# 02_EFR32xG1x_DISC_REF_DES_A00_RfAntPower.net
KiCad netlist of a schematic drawn in Altium Designer
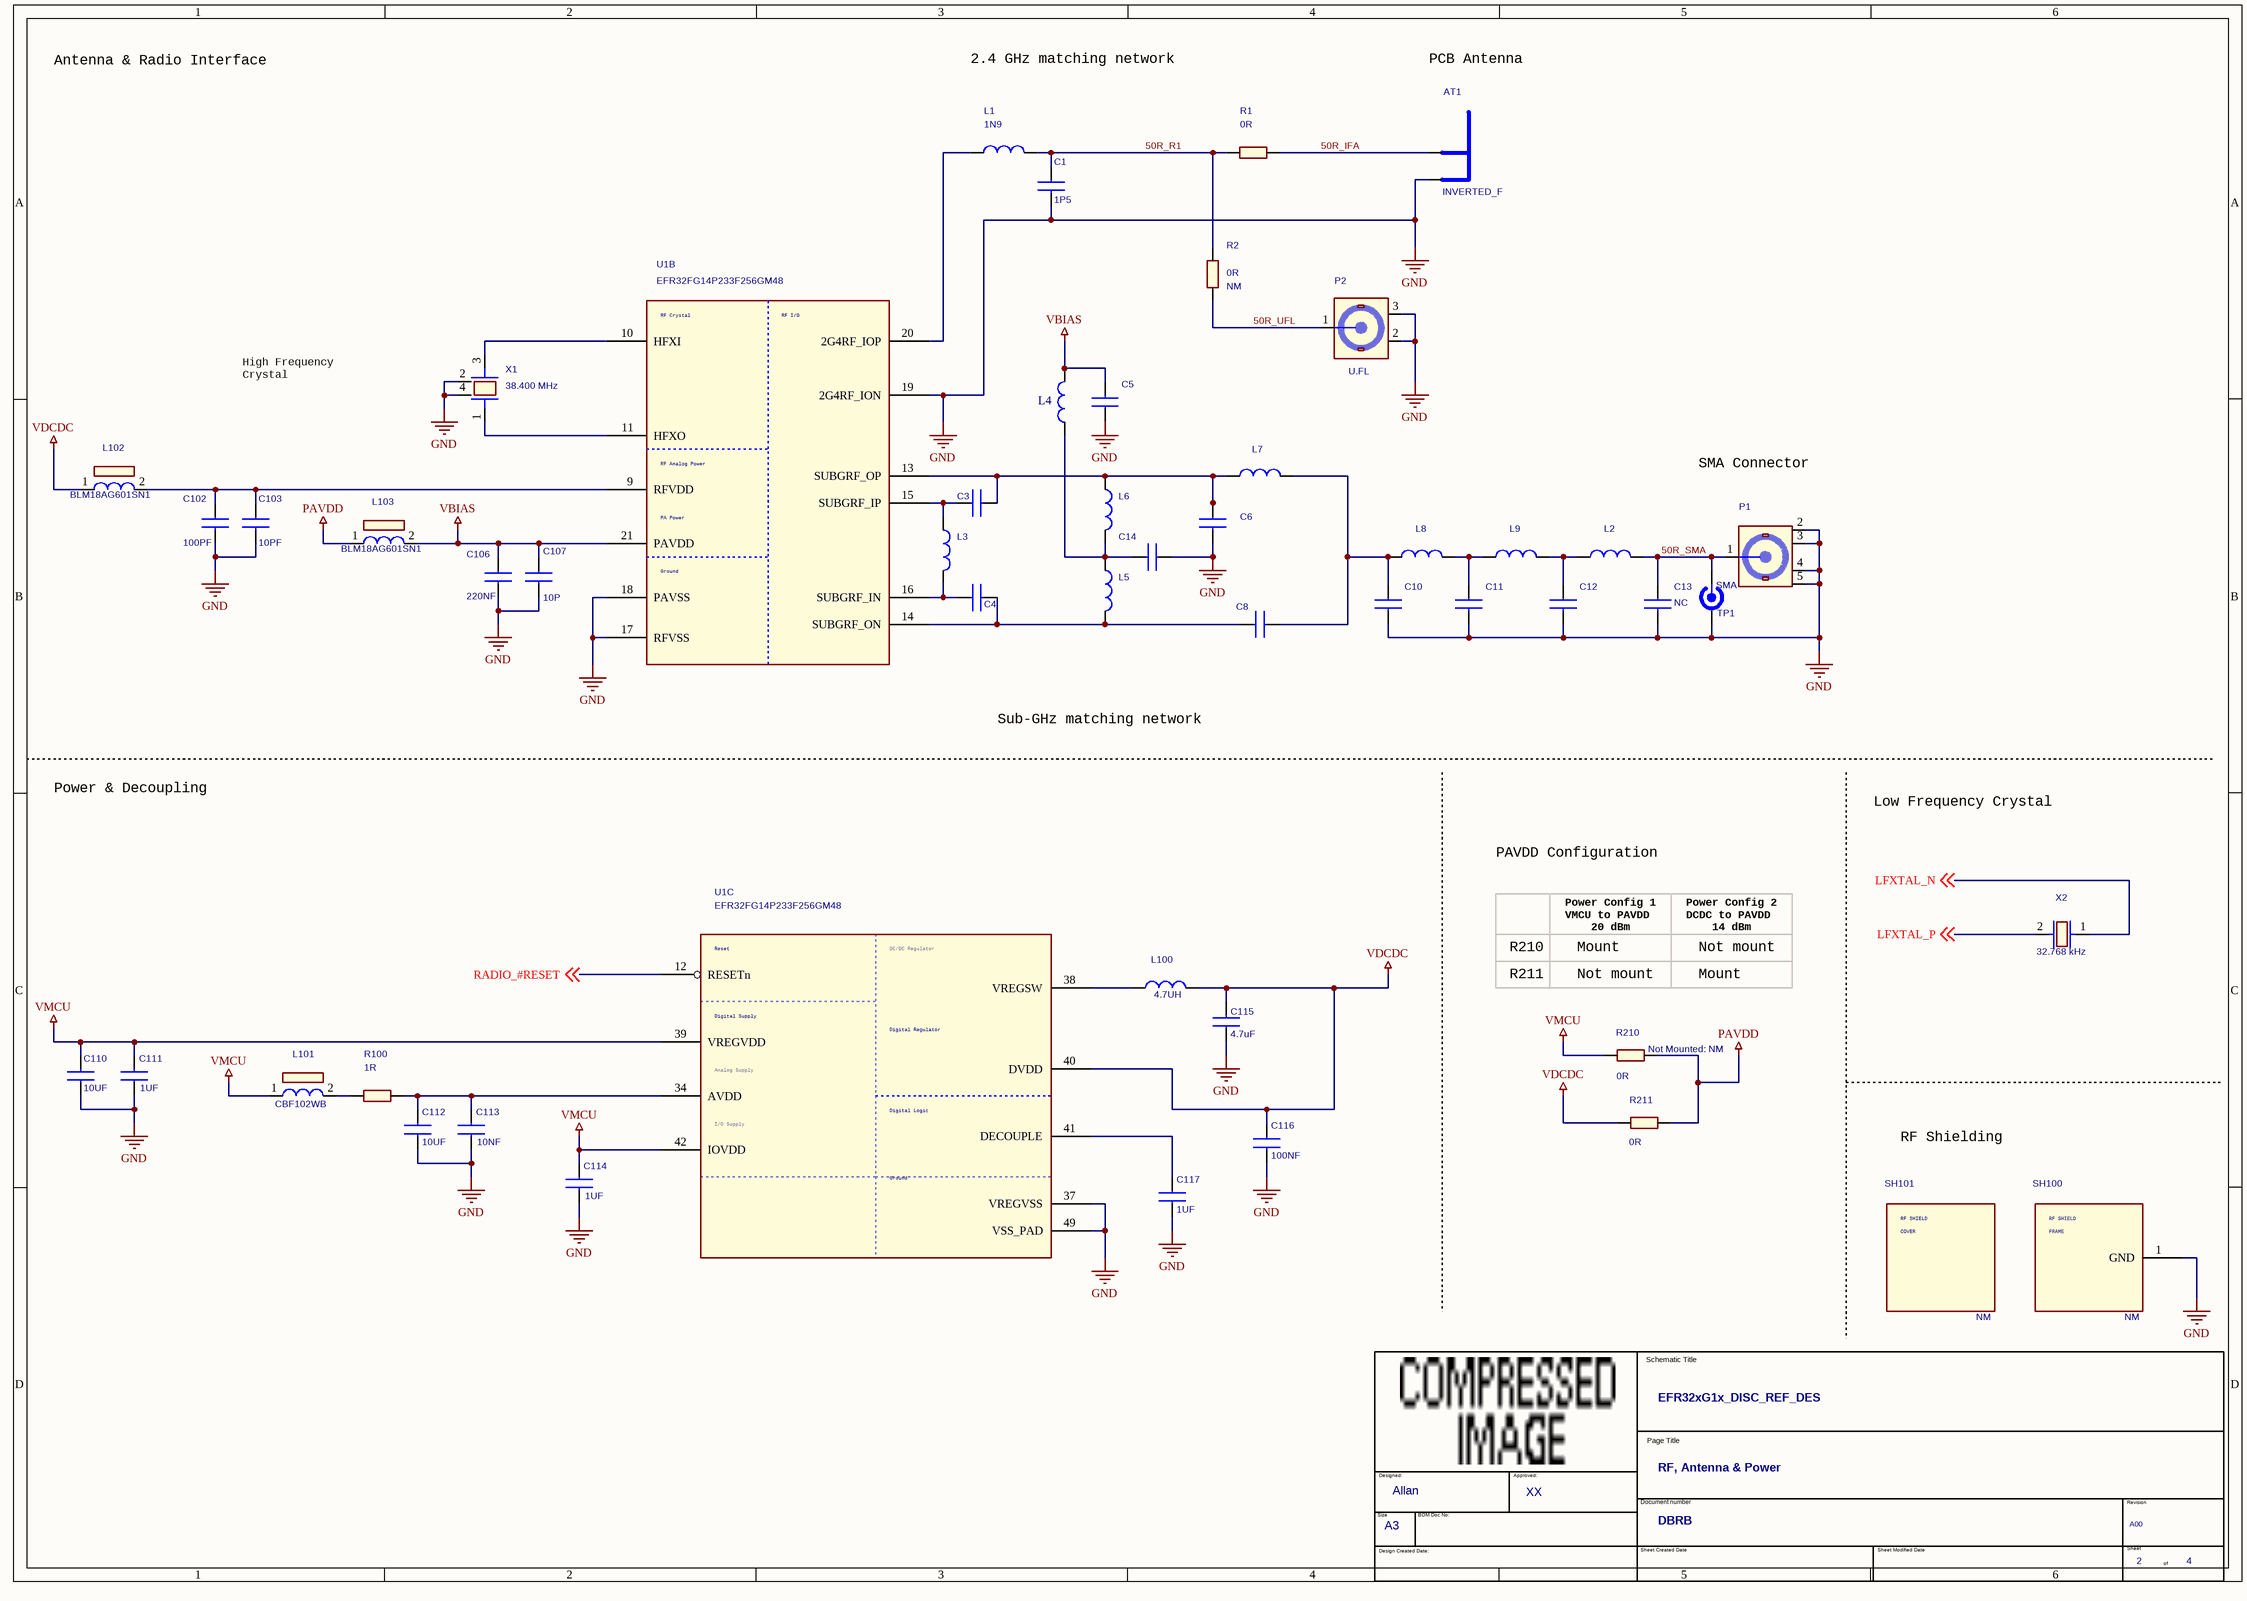
[diagram p0: 02_EFR32xG1x_DISC_REF_DES_A00_RfAntPower.SchDoc]

(export (version "E")
  (design (tool "Eeschema 10.0.6"))
  (components
    (comp (ref "AT1")
      (value "INVERTED_F")
      (footprint "ANT_INV_F_2.4_GHZ_17.3MM_MIR")
      (libsource (lib "*") (part "ANT_INVERTED_F"))
    )
    (comp (ref "C1")
      (value "1P5")
      (footprint "C0201_L")
      (fields (field (name "TOLERANCE") "?.05P") (field (name "MFG") "Murata"))
      (libsource (lib "*") (part "C0402"))
    )
    (comp (ref "C3")
      (value "1P8")
      (footprint "C0201_L")
      (fields (field (name "TOLERANCE") "?.05P") (field (name "MFG") "Murata"))
      (libsource (lib "*") (part "C0402"))
    )
    (comp (ref "C4")
      (value "1P8")
      (footprint "C0201_L")
      (fields (field (name "TOLERANCE") "?.05P") (field (name "MFG") "Murata"))
      (libsource (lib "*") (part "C0402"))
    )
    (comp (ref "C5")
      (value "270pF")
      (footprint "C0201_L")
      (fields (field (name "TOLERANCE") "?.1P") (field (name "MFG") "Murata"))
      (libsource (lib "*") (part "C0402"))
    )
    (comp (ref "C6") (value "5.1P") (footprint "C0201_L") (libsource (lib "*") (part "C0402")))
    (comp (ref "C8")
      (value "4P7")
      (footprint "C0201_L")
      (fields (field (name "TOLERANCE") "?%") (field (name "MFG") "Murata"))
      (libsource (lib "*") (part "C0402"))
    )
    (comp (ref "C10")
      (value "6P2")
      (footprint "C0201_L")
      (fields (field (name "TOLERANCE") "?.1P") (field (name "MFG") "Murata"))
      (libsource (lib "*") (part "C0402"))
    )
    (comp (ref "C11")
      (value "5.6P")
      (footprint "C0201_L")
      (fields (field (name "TOLERANCE") "?%") (field (name "MFG") "Murata"))
      (libsource (lib "*") (part "C0402"))
    )
    (comp (ref "C12")
      (value "5P6")
      (footprint "C0201_L")
      (fields (field (name "TOLERANCE") "?.05pF") (field (name "MFG") "Murata"))
      (libsource (lib "*") (part "C0402"))
    )
    (comp (ref "C13")
      (value "NC")
      (footprint "C0201_L")
      (fields (field (name "TOLERANCE") "?.05pF") (field (name "MFG") "Murata"))
      (libsource (lib "*") (part "C0402"))
    )
    (comp (ref "C14")
      (value "2P")
      (footprint "C0201_L")
      (fields (field (name "TOLERANCE") "?%") (field (name "MFG") "Murata"))
      (libsource (lib "*") (part "C0402"))
    )
    (comp (ref "C102")
      (value "100PF")
      (footprint "C0402_L")
      (fields (field (name "TOLERANCE") "5%"))
      (libsource (lib "*") (part "C0402"))
    )
    (comp (ref "C103")
      (value "10PF")
      (footprint "C0402_L")
      (fields (field (name "TOLERANCE") "5%"))
      (libsource (lib "*") (part "C0402"))
    )
    (comp (ref "C106")
      (value "220NF")
      (footprint "C0402_L")
      (fields (field (name "TOLERANCE") "10%"))
      (libsource (lib "*") (part "C0402"))
    )
    (comp (ref "C107")
      (value "10P")
      (footprint "C0201_L")
      (fields (field (name "TOLERANCE") "5%"))
      (libsource (lib "*") (part "C0402"))
    )
    (comp (ref "C110")
      (value "10UF")
      (footprint "C0603_L")
      (fields (field (name "TOLERANCE") "20%"))
      (libsource (lib "*") (part "C0603"))
    )
    (comp (ref "C111")
      (value "1UF")
      (footprint "C0402_L")
      (fields (field (name "TOLERANCE") "10%"))
      (libsource (lib "*") (part "C0402"))
    )
    (comp (ref "C112")
      (value "10UF")
      (footprint "C0603_L")
      (fields (field (name "TOLERANCE") "20%"))
      (libsource (lib "*") (part "C0603"))
    )
    (comp (ref "C113")
      (value "10NF")
      (footprint "C0402_L")
      (fields (field (name "TOLERANCE") "10%"))
      (libsource (lib "*") (part "C0402"))
    )
    (comp (ref "C114")
      (value "1UF")
      (footprint "C0402_L")
      (fields (field (name "TOLERANCE") "10%"))
      (libsource (lib "*") (part "C0402"))
    )
    (comp (ref "C115")
      (value "4.7uF")
      (footprint "C0402_L")
      (fields (field (name "TOLERANCE") "10%"))
      (libsource (lib "*") (part "C0402"))
    )
    (comp (ref "C116")
      (value "100NF")
      (footprint "C0402_L")
      (fields (field (name "TOLERANCE") "10%"))
      (libsource (lib "*") (part "C0402"))
    )
    (comp (ref "C117")
      (value "1UF")
      (footprint "C0402_L")
      (fields (field (name "TOLERANCE") "10%"))
      (libsource (lib "*") (part "C0402"))
    )
    (comp (ref "L1")
      (value "1N9")
      (footprint "COIL_0201_L")
      (fields (field (name "MFG") "Murata") (field (name "TOLERANCE") "?.05N"))
      (libsource (lib "") (part "L0402_1"))
    )
    (comp (ref "L2")
      (value "120P")
      (footprint "COIL_0201_L")
      (fields (field (name "MFG") "Murata") (field (name "TOLERANCE") "?%"))
      (libsource (lib "*") (part "L0402"))
    )
    (comp (ref "L3") (value "75NH") (footprint "COIL_0201_L") (libsource (lib "BRD4259B") (part "L0402")))
    (comp (ref "L4")
      (value "330NH")
      (footprint "COIL_0402_L")
      (libsource (lib "BRD4259A_Library") (part "L0603"))
    )
    (comp (ref "L5")
      (value "12NH")
      (footprint "COIL_0201_L")
      (libsource (lib "BRD4259A_Library") (part "L0402"))
    )
    (comp (ref "L6")
      (value "12NH")
      (footprint "COIL_0201_L")
      (libsource (lib "BRD4259A_Library") (part "L0402"))
    )
    (comp (ref "L7")
      (value "27NH")
      (footprint "COIL_0201_L")
      (fields (field (name "MFG") "Murata") (field (name "TOLERANCE") "?%"))
      (libsource (lib "*") (part "L0402"))
    )
    (comp (ref "L8")
      (value "24NH")
      (footprint "COIL_0201_L")
      (fields (field (name "MFG") "Murata") (field (name "TOLERANCE") "?%"))
      (libsource (lib "*") (part "L0402"))
    )
    (comp (ref "L9")
      (value "24NH")
      (footprint "COIL_0201_L")
      (fields (field (name "MFG") "Murata") (field (name "TOLERANCE") "?%"))
      (libsource (lib "*") (part "L0402"))
    )
    (comp (ref "L100")
      (value "4.7UH")
      (footprint "COIL_MUR_LQH3NP_1212")
      (fields (field (name "MFG") "Murata"))
      (libsource (lib "*") (part "LQH3NP"))
    )
    (comp (ref "L101")
      (value "CBF102WB")
      (footprint "WURTH_CBF_0603")
      (fields (field (name "MFG") "W黵th Electronics"))
      (libsource (lib "*") (part "CBF102WB"))
    )
    (comp (ref "L102")
      (value "BLM18AG601SN1")
      (footprint "COIL_MUR_BLM18_0603")
      (fields (field (name "MFG") "Murata"))
      (libsource (lib "*") (part "BLM18AG"))
    )
    (comp (ref "L103")
      (value "BLM18AG601SN1")
      (footprint "COIL_MUR_BLM18_0603")
      (fields (field (name "MFG") "Murata"))
      (libsource (lib "*") (part "BLM18AG"))
    )
    (comp (ref "P1")
      (value "SMA")
      (footprint "TE_SMA_TH_1814832")
      (fields (field (name "MFG") "TE Connectivity"))
      (libsource (lib "*") (part "SMA_TH"))
    )
    (comp (ref "P2")
      (value "U.FL")
      (footprint "HIROSE_U.FL-R-SMT-1")
      (fields (field (name "MFG") "Hirose"))
      (libsource (lib "*") (part "HIROSE_U.FL"))
    )
    (comp (ref "R1") (value "0R") (footprint "R0402_L") (libsource (lib "") (part "R0402_2")))
    (comp (ref "R2")
      (value "0R")
      (footprint "R0402_L")
      (fields (field (name "NOT MOUNTED") "NM"))
      (libsource (lib "*") (part "R0402"))
    )
    (comp (ref "R100") (value "1R") (footprint "R0402_L") (libsource (lib "") (part "R0402_2")))
    (comp (ref "R210")
      (value "0R")
      (footprint "R0402_L")
      (fields (field (name "NOT MOUNTED") "NM"))
      (libsource (lib "") (part "R0402_1"))
    )
    (comp (ref "R211") (value "0R") (footprint "R0402_L") (libsource (lib "") (part "R0402_1")))
    (comp (ref "SH100")
      (value "RF_SHIELD_FRAME_BMI-S-203-F")
      (footprint "RF_SHIELD_FRAME_BMI-S-203-F_PCB4100")
      (fields (field (name "MFG") "Laird Technologies") (field (name "NOT MOUNTED") "NM"))
      (libsource (lib "*") (part "RF_SHIELD_FRAME_BMI-S-203-F"))
    )
    (comp (ref "SH101")
      (value "RF_SHIELD_COVER_BMI-S-203-C")
      (fields (field (name "NOT MOUNTED") "NM") (field (name "MFG") "Laird Technologies"))
      (libsource (lib "*") (part "RF_SHIELD_COVER_BMI-S-203-C"))
    )
    (comp (ref "TP1")
      (value "RF_TEST_POINT")
      (footprint "TP_INGUN_50_OHM_CLOSED openvia")
      (libsource (lib "*") (part "TP_RF"))
    )
    (comp (ref "U1")
      (value "EFR32FG14P233F256GM48")
      (footprint "QFN48_M050_SQ7.0_EP_SL_L")
      (fields (field (name "MFG") "Silicon Labs"))
      (libsource (lib "*") (part "EFR32-DUALBAND-QFN48"))
    )
    (comp (ref "X1")
      (value "38.400 MHz")
      (footprint "X_SSS_DSX211SH_2.05X1.65-4")
      (fields (field (name "MFG") "KDS"))
      (libsource (lib "*") (part "DSX211SH"))
    )
    (comp (ref "X2")
      (value "32.768 kHz")
      (footprint "X_MCS_CM8V-T1A")
      (fields (field (name "MFG") "KDS"))
      (libsource (lib "*") (part "CM8V-T1A"))
    )
  )
  (nets
    (net (code "1") (name "/50R_IFA") (class "Default")
      (node (ref "AT1") (pin "1") (pinfunction "ANT_1") (pintype "passive"))
      (node (ref "R1") (pin "2") (pinfunction "2_2") (pintype "passive"))
    )
    (net (code "2") (name "/50R_R1") (class "Default")
      (node (ref "C1") (pin "2") (pinfunction "2_2") (pintype "passive"))
      (node (ref "L1") (pin "2") (pinfunction "2_2") (pintype "passive"))
      (node (ref "R1") (pin "1") (pinfunction "1_1") (pintype "passive"))
      (node (ref "R2") (pin "1") (pinfunction "1_1") (pintype "passive"))
    )
    (net (code "3") (name "/50R_SMA") (class "Default")
      (node (ref "C13") (pin "1") (pinfunction "1_1") (pintype "passive"))
      (node (ref "L2") (pin "1") (pinfunction "1_1") (pintype "passive"))
      (node (ref "P1") (pin "1") (pinfunction "SIGNAL_1") (pintype "passive"))
      (node (ref "TP1") (pin "1") (pinfunction "RF_1") (pintype "passive"))
    )
    (net (code "4") (name "/50R_UFL") (class "Default")
      (node (ref "P2") (pin "1") (pinfunction "SIGNAL_1") (pintype "passive"))
      (node (ref "R2") (pin "2") (pinfunction "2_2") (pintype "passive"))
    )
    (net (code "5") (name "GND") (class "Default")
      (node (ref "AT1") (pin "2") (pinfunction "GND_2") (pintype "passive"))
      (node (ref "C1") (pin "1") (pinfunction "1_1") (pintype "passive"))
      (node (ref "C10") (pin "2") (pinfunction "2_2") (pintype "passive"))
      (node (ref "C102") (pin "2") (pinfunction "2_2") (pintype "passive"))
      (node (ref "C103") (pin "2") (pinfunction "2_2") (pintype "passive"))
      (node (ref "C106") (pin "2") (pinfunction "2_2") (pintype "passive"))
      (node (ref "C107") (pin "2") (pinfunction "2_2") (pintype "passive"))
      (node (ref "C11") (pin "2") (pinfunction "2_2") (pintype "passive"))
      (node (ref "C110") (pin "2") (pinfunction "2_2") (pintype "passive"))
      (node (ref "C111") (pin "2") (pinfunction "2_2") (pintype "passive"))
      (node (ref "C112") (pin "2") (pinfunction "2_2") (pintype "passive"))
      (node (ref "C113") (pin "2") (pinfunction "2_2") (pintype "passive"))
      (node (ref "C114") (pin "2") (pinfunction "2_2") (pintype "passive"))
      (node (ref "C115") (pin "2") (pinfunction "2_2") (pintype "passive"))
      (node (ref "C116") (pin "2") (pinfunction "2_2") (pintype "passive"))
      (node (ref "C117") (pin "2") (pinfunction "2_2") (pintype "passive"))
      (node (ref "C12") (pin "2") (pinfunction "2_2") (pintype "passive"))
      (node (ref "C13") (pin "2") (pinfunction "2_2") (pintype "passive"))
      (node (ref "C14") (pin "2") (pinfunction "2_2") (pintype "passive"))
      (node (ref "C5") (pin "2") (pinfunction "2_2") (pintype "passive"))
      (node (ref "C6") (pin "2") (pinfunction "2_2") (pintype "passive"))
      (node (ref "P1") (pin "2") (pinfunction "GND1_2") (pintype "passive"))
      (node (ref "P1") (pin "3") (pinfunction "GND2_3") (pintype "passive"))
      (node (ref "P1") (pin "4") (pinfunction "GND3_4") (pintype "passive"))
      (node (ref "P1") (pin "5") (pinfunction "GND4_5") (pintype "passive"))
      (node (ref "P2") (pin "2") (pinfunction "GND1_2") (pintype "passive"))
      (node (ref "P2") (pin "3") (pinfunction "GND4_3") (pintype "passive"))
      (node (ref "SH100") (pin "1") (pinfunction "GND_1") (pintype "passive"))
      (node (ref "TP1") (pin "2") (pinfunction "GND_2") (pintype "power_in"))
      (node (ref "U1") (pin "17") (pinfunction "RFVSS_17") (pintype "passive"))
      (node (ref "U1") (pin "18") (pinfunction "PAVSS_18") (pintype "passive"))
      (node (ref "U1") (pin "19") (pinfunction "2G4RF_ION_19") (pintype "passive"))
      (node (ref "U1") (pin "37") (pinfunction "VREGVSS_37") (pintype "passive"))
      (node (ref "U1") (pin "49") (pinfunction "VSS_PAD_49") (pintype "power_in"))
      (node (ref "X1") (pin "2") (pinfunction "2_2") (pintype "passive"))
      (node (ref "X1") (pin "4") (pinfunction "4_4") (pintype "passive"))
    )
    (net (code "6") (name "LFXTAL_N") (class "Default")
      (node (ref "X2") (pin "1") (pinfunction "1_1") (pintype "passive"))
    )
    (net (code "7") (name "LFXTAL_P") (class "Default")
      (node (ref "X2") (pin "2") (pinfunction "2_2") (pintype "passive"))
    )
    (net (code "8") (name "Net-(C10-Pad1)") (class "Default")
      (node (ref "C10") (pin "1") (pinfunction "1_1") (pintype "passive"))
      (node (ref "C8") (pin "1") (pinfunction "1_1") (pintype "passive"))
      (node (ref "L7") (pin "1") (pinfunction "1_1") (pintype "passive"))
      (node (ref "L8") (pin "2") (pinfunction "2_2") (pintype "passive"))
    )
    (net (code "9") (name "Net-(C11-Pad1)") (class "Default")
      (node (ref "C11") (pin "1") (pinfunction "1_1") (pintype "passive"))
      (node (ref "L8") (pin "1") (pinfunction "1_1") (pintype "passive"))
      (node (ref "L9") (pin "2") (pinfunction "2_2") (pintype "passive"))
    )
    (net (code "10") (name "Net-(C12-Pad1)") (class "Default")
      (node (ref "C12") (pin "1") (pinfunction "1_1") (pintype "passive"))
      (node (ref "L2") (pin "2") (pinfunction "2_2") (pintype "passive"))
      (node (ref "L9") (pin "1") (pinfunction "1_1") (pintype "passive"))
    )
    (net (code "11") (name "Net-(C14-Pad1)") (class "Default")
      (node (ref "C14") (pin "1") (pinfunction "1_1") (pintype "passive"))
      (node (ref "L4") (pin "2") (pinfunction "2_2") (pintype "passive"))
      (node (ref "L5") (pin "1") (pinfunction "1_1") (pintype "passive"))
      (node (ref "L6") (pin "2") (pinfunction "2_2") (pintype "passive"))
    )
    (net (code "12") (name "Net-(L101-Pad2)") (class "Default")
      (node (ref "L101") (pin "2") (pinfunction "2_2") (pintype "passive"))
      (node (ref "R100") (pin "1") (pinfunction "1_1") (pintype "passive"))
    )
    (net (code "13") (name "Net-(U1B-2G4RF_IOP)") (class "Default")
      (node (ref "L1") (pin "1") (pinfunction "1_1") (pintype "passive"))
      (node (ref "U1") (pin "20") (pinfunction "2G4RF_IOP_20") (pintype "passive"))
    )
    (net (code "14") (name "Net-(U1B-HFXI)") (class "Default")
      (node (ref "U1") (pin "10") (pinfunction "HFXI_10") (pintype "passive"))
      (node (ref "X1") (pin "3") (pinfunction "3_3") (pintype "passive"))
    )
    (net (code "15") (name "Net-(U1B-HFXO)") (class "Default")
      (node (ref "U1") (pin "11") (pinfunction "HFXO_11") (pintype "passive"))
      (node (ref "X1") (pin "1") (pinfunction "1_1") (pintype "passive"))
    )
    (net (code "16") (name "Net-(U1B-RFVDD)") (class "Default")
      (node (ref "C102") (pin "1") (pinfunction "1_1") (pintype "passive"))
      (node (ref "C103") (pin "1") (pinfunction "1_1") (pintype "passive"))
      (node (ref "L102") (pin "2") (pinfunction "2_2") (pintype "passive"))
      (node (ref "U1") (pin "9") (pinfunction "RFVDD_9") (pintype "power_in"))
    )
    (net (code "17") (name "Net-(U1B-SUBGRF_IN)") (class "Default")
      (node (ref "C4") (pin "2") (pinfunction "2_2") (pintype "passive"))
      (node (ref "L3") (pin "2") (pinfunction "2_2") (pintype "passive"))
      (node (ref "U1") (pin "16") (pinfunction "SUBGRF_IN_16") (pintype "passive"))
    )
    (net (code "18") (name "Net-(U1B-SUBGRF_IP)") (class "Default")
      (node (ref "C3") (pin "2") (pinfunction "2_2") (pintype "passive"))
      (node (ref "L3") (pin "1") (pinfunction "1_1") (pintype "passive"))
      (node (ref "U1") (pin "15") (pinfunction "SUBGRF_IP_15") (pintype "passive"))
    )
    (net (code "19") (name "Net-(U1B-SUBGRF_ON)") (class "Default")
      (node (ref "C4") (pin "1") (pinfunction "1_1") (pintype "passive"))
      (node (ref "C8") (pin "2") (pinfunction "2_2") (pintype "passive"))
      (node (ref "L5") (pin "2") (pinfunction "2_2") (pintype "passive"))
      (node (ref "U1") (pin "14") (pinfunction "SUBGRF_ON_14") (pintype "passive"))
    )
    (net (code "20") (name "Net-(U1B-SUBGRF_OP)") (class "Default")
      (node (ref "C3") (pin "1") (pinfunction "1_1") (pintype "passive"))
      (node (ref "C6") (pin "1") (pinfunction "1_1") (pintype "passive"))
      (node (ref "L6") (pin "1") (pinfunction "1_1") (pintype "passive"))
      (node (ref "L7") (pin "2") (pinfunction "2_2") (pintype "passive"))
      (node (ref "U1") (pin "13") (pinfunction "SUBGRF_OP_13") (pintype "passive"))
    )
    (net (code "21") (name "Net-(U1C-AVDD)") (class "Default")
      (node (ref "C112") (pin "1") (pinfunction "1_1") (pintype "passive"))
      (node (ref "C113") (pin "1") (pinfunction "1_1") (pintype "passive"))
      (node (ref "R100") (pin "2") (pinfunction "2_2") (pintype "passive"))
      (node (ref "U1") (pin "34") (pinfunction "AVDD_34") (pintype "power_in"))
    )
    (net (code "22") (name "Net-(U1C-DECOUPLE)") (class "Default")
      (node (ref "C117") (pin "1") (pinfunction "1_1") (pintype "passive"))
      (node (ref "U1") (pin "41") (pinfunction "DECOUPLE_41") (pintype "power_in"))
    )
    (net (code "23") (name "Net-(U1C-VREGSW)") (class "Default")
      (node (ref "L100") (pin "1") (pinfunction "1_1") (pintype "passive"))
      (node (ref "U1") (pin "38") (pinfunction "VREGSW_38") (pintype "passive"))
    )
    (net (code "24") (name "PAVDD") (class "Default")
      (node (ref "L103") (pin "1") (pinfunction "1_1") (pintype "passive"))
      (node (ref "R210") (pin "1") (pinfunction "1_1") (pintype "passive"))
      (node (ref "R211") (pin "1") (pinfunction "1_1") (pintype "passive"))
    )
    (net (code "25") (name "RADIO_#RESET") (class "Default")
      (node (ref "U1") (pin "12") (pinfunction "RESETn_12") (pintype "passive"))
    )
    (net (code "26") (name "VBIAS") (class "Default")
      (node (ref "C106") (pin "1") (pinfunction "1_1") (pintype "passive"))
      (node (ref "C107") (pin "1") (pinfunction "1_1") (pintype "passive"))
      (node (ref "C5") (pin "1") (pinfunction "1_1") (pintype "passive"))
      (node (ref "L103") (pin "2") (pinfunction "2_2") (pintype "passive"))
      (node (ref "L4") (pin "1") (pinfunction "1_1") (pintype "passive"))
      (node (ref "U1") (pin "21") (pinfunction "PAVDD_21") (pintype "passive"))
    )
    (net (code "27") (name "VDCDC") (class "Default")
      (node (ref "C115") (pin "1") (pinfunction "1_1") (pintype "passive"))
      (node (ref "C116") (pin "1") (pinfunction "1_1") (pintype "passive"))
      (node (ref "L100") (pin "2") (pinfunction "2_2") (pintype "passive"))
      (node (ref "L102") (pin "1") (pinfunction "1_1") (pintype "passive"))
      (node (ref "R211") (pin "2") (pinfunction "2_2") (pintype "passive"))
      (node (ref "U1") (pin "40") (pinfunction "DVDD_40") (pintype "power_in"))
    )
    (net (code "28") (name "VMCU") (class "Default")
      (node (ref "C110") (pin "1") (pinfunction "1_1") (pintype "passive"))
      (node (ref "C111") (pin "1") (pinfunction "1_1") (pintype "passive"))
      (node (ref "C114") (pin "1") (pinfunction "1_1") (pintype "passive"))
      (node (ref "L101") (pin "1") (pinfunction "1_1") (pintype "passive"))
      (node (ref "R210") (pin "2") (pinfunction "2_2") (pintype "passive"))
      (node (ref "U1") (pin "39") (pinfunction "VREGVDD_39") (pintype "passive"))
      (node (ref "U1") (pin "42") (pinfunction "IOVDD_42") (pintype "power_in"))
    )
  )
)
